# DummyLoad.net
KiCad netlist of a schematic drawn in EAGLE
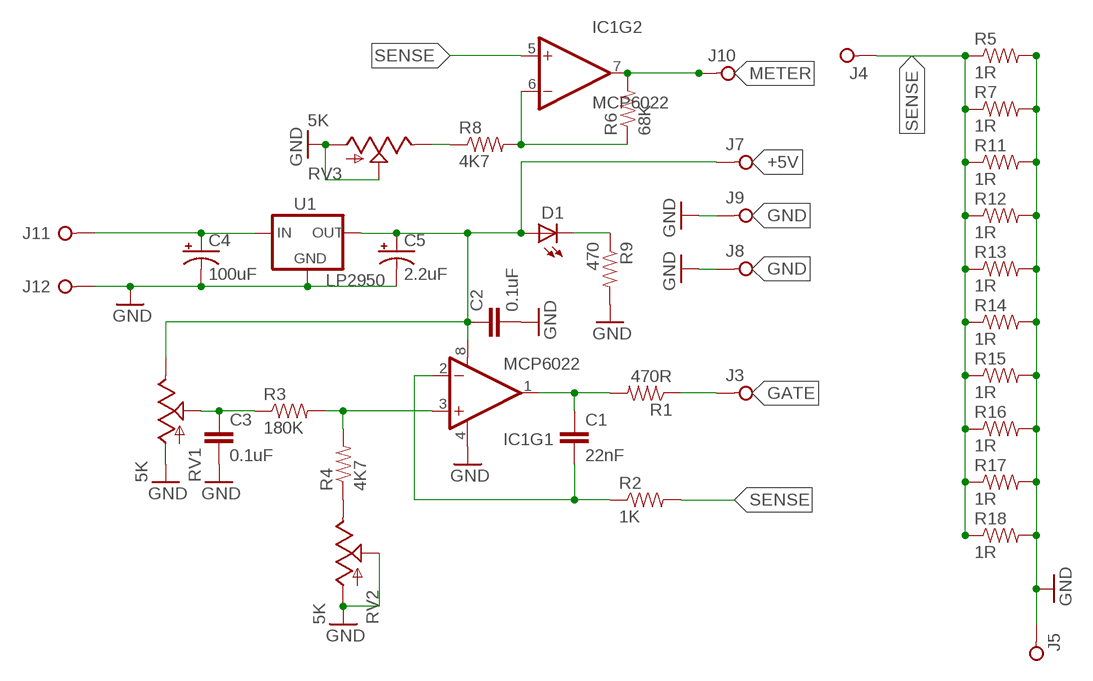
[diagram p0: schematic, sheet 1]

(export (version "E")
  (design (tool "Eeschema 10.0.6"))
  (components
    (comp (ref "C1")
      (value "22nF")
      (footprint "eagle-import:CAPACITOR-5MM")
      (libsource (lib "eagle-import") (part "CAPACITOR-5MM"))
    )
    (comp (ref "C2")
      (value "0.1uF")
      (footprint "eagle-import:CAPACITOR-5MM")
      (libsource (lib "eagle-import") (part "CAPACITOR-5MM"))
    )
    (comp (ref "C3")
      (value "0.1uF")
      (footprint "eagle-import:CAPACITOR-5MM")
      (libsource (lib "eagle-import") (part "CAPACITOR-5MM"))
    )
    (comp (ref "C4")
      (value "100uF")
      (footprint "eagle-import:CAP-POL-2.5-6")
      (libsource (lib "eagle-import") (part "CAP-POL-2.5-6"))
    )
    (comp (ref "C5")
      (value "2.2uF")
      (footprint "eagle-import:CAP-POL-2.5-5")
      (libsource (lib "eagle-import") (part "CAP-POL-2.5-5"))
    )
    (comp (ref "D1")
      (value "LED-5MM")
      (footprint "eagle-import:LED5MM")
      (libsource (lib "eagle-import") (part "LED-5MM"))
    )
    (comp (ref "IC1")
      (value "MCP6022")
      (footprint "eagle-import:DIP08")
      (libsource (lib "eagle-import") (part "MCP6022"))
    )
    (comp (ref "J1")
      (value "PINHD-1X2")
      (footprint "eagle-import:1X02")
      (libsource (lib "eagle-import") (part "PINHD-1X2"))
    )
    (comp (ref "J3")
      (value "PINHD-1X1")
      (footprint "eagle-import:1X01")
      (libsource (lib "eagle-import") (part "PINHD-1X1"))
    )
    (comp (ref "J4")
      (value "PINHD-1X1")
      (footprint "eagle-import:1X01")
      (libsource (lib "eagle-import") (part "PINHD-1X1"))
    )
    (comp (ref "J5")
      (value "PINHD-1X1")
      (footprint "eagle-import:1X01")
      (libsource (lib "eagle-import") (part "PINHD-1X1"))
    )
    (comp (ref "J7")
      (value "PINHD-1X1")
      (footprint "eagle-import:1X01")
      (libsource (lib "eagle-import") (part "PINHD-1X1"))
    )
    (comp (ref "J8")
      (value "PINHD-1X1")
      (footprint "eagle-import:1X01")
      (libsource (lib "eagle-import") (part "PINHD-1X1"))
    )
    (comp (ref "J9")
      (value "PINHD-1X1")
      (footprint "eagle-import:1X01")
      (libsource (lib "eagle-import") (part "PINHD-1X1"))
    )
    (comp (ref "J10")
      (value "PINHD-1X1")
      (footprint "eagle-import:1X01")
      (libsource (lib "eagle-import") (part "PINHD-1X1"))
    )
    (comp (ref "R1")
      (value "470R")
      (footprint "eagle-import:AXIAL-7.5MM")
      (libsource (lib "eagle-import") (part "RESISTOR-7.5MM"))
    )
    (comp (ref "R2")
      (value "1K")
      (footprint "eagle-import:AXIAL-7.5MM")
      (libsource (lib "eagle-import") (part "RESISTOR-7.5MM"))
    )
    (comp (ref "R3")
      (value "180K")
      (footprint "eagle-import:AXIAL-7.5MM")
      (libsource (lib "eagle-import") (part "RESISTOR-7.5MM"))
    )
    (comp (ref "R4")
      (value "4K7")
      (footprint "eagle-import:AXIAL-7.5MM")
      (libsource (lib "eagle-import") (part "RESISTOR-7.5MM"))
    )
    (comp (ref "R5")
      (value "1R")
      (footprint "eagle-import:AXIAL-7.5MM")
      (libsource (lib "eagle-import") (part "RESISTOR-7.5MM"))
    )
    (comp (ref "R6")
      (value "68K")
      (footprint "eagle-import:AXIAL-7.5MM")
      (libsource (lib "eagle-import") (part "RESISTOR-7.5MM"))
    )
    (comp (ref "R7")
      (value "1R")
      (footprint "eagle-import:AXIAL-7.5MM")
      (libsource (lib "eagle-import") (part "RESISTOR-7.5MM"))
    )
    (comp (ref "R8")
      (value "4K7")
      (footprint "eagle-import:AXIAL-7.5MM")
      (libsource (lib "eagle-import") (part "RESISTOR-7.5MM"))
    )
    (comp (ref "R9")
      (value "470")
      (footprint "eagle-import:AXIAL-7.5MM")
      (libsource (lib "eagle-import") (part "RESISTOR-7.5MM"))
    )
    (comp (ref "R11")
      (value "1R")
      (footprint "eagle-import:AXIAL-7.5MM")
      (libsource (lib "eagle-import") (part "RESISTOR-7.5MM"))
    )
    (comp (ref "R12")
      (value "1R")
      (footprint "eagle-import:AXIAL-7.5MM")
      (libsource (lib "eagle-import") (part "RESISTOR-7.5MM"))
    )
    (comp (ref "R13")
      (value "1R")
      (footprint "eagle-import:AXIAL-7.5MM")
      (libsource (lib "eagle-import") (part "RESISTOR-7.5MM"))
    )
    (comp (ref "R14")
      (value "1R")
      (footprint "eagle-import:AXIAL-7.5MM")
      (libsource (lib "eagle-import") (part "RESISTOR-7.5MM"))
    )
    (comp (ref "R15")
      (value "1R")
      (footprint "eagle-import:AXIAL-7.5MM")
      (libsource (lib "eagle-import") (part "RESISTOR-7.5MM"))
    )
    (comp (ref "R16")
      (value "1R")
      (footprint "eagle-import:AXIAL-7.5MM")
      (libsource (lib "eagle-import") (part "RESISTOR-7.5MM"))
    )
    (comp (ref "R17")
      (value "1R")
      (footprint "eagle-import:AXIAL-7.5MM")
      (libsource (lib "eagle-import") (part "RESISTOR-7.5MM"))
    )
    (comp (ref "R18")
      (value "1R")
      (footprint "eagle-import:AXIAL-7.5MM")
      (libsource (lib "eagle-import") (part "RESISTOR-7.5MM"))
    )
    (comp (ref "RV1")
      (value "5K")
      (footprint "eagle-import:1X03")
      (libsource (lib "eagle-import") (part "POT-OFFBRD"))
    )
    (comp (ref "RV2")
      (value "5K")
      (footprint "eagle-import:TRIM_POT")
      (libsource (lib "eagle-import") (part "POTTRIM"))
    )
    (comp (ref "RV3")
      (value "5K")
      (footprint "eagle-import:TRIM_POT")
      (libsource (lib "eagle-import") (part "POTTRIM"))
    )
    (comp (ref "U1")
      (value "LP2950")
      (footprint "eagle-import:TO92-INLINE")
      (libsource (lib "eagle-import") (part "LP2950"))
    )
  )
  (nets
    (net (code "1") (name "+5V") (class "Default")
      (node (ref "C2") (pin "1") (pinfunction "1_1") (pintype "passive"))
      (node (ref "C5") (pin "+") (pinfunction "+_+") (pintype "passive"))
      (node (ref "D1") (pin "A") (pinfunction "A_A") (pintype "passive"))
      (node (ref "IC1") (pin "8") (pinfunction "V+_8") (pintype "power_in"))
      (node (ref "J7") (pin "1") (pinfunction "KL_1") (pintype "passive"))
      (node (ref "RV1") (pin "3") (pinfunction "E_3") (pintype "passive"))
      (node (ref "U1") (pin "1") (pinfunction "OUT_1") (pintype "passive"))
    )
    (net (code "2") (name "GATE") (class "Default")
      (node (ref "J3") (pin "1") (pinfunction "KL_1") (pintype "passive"))
      (node (ref "R1") (pin "P$1") (pinfunction "1_P$1") (pintype "passive"))
    )
    (net (code "3") (name "GND") (class "Default")
      (node (ref "C2") (pin "2") (pinfunction "2_2") (pintype "passive"))
      (node (ref "C3") (pin "2") (pinfunction "2_2") (pintype "passive"))
      (node (ref "C4") (pin "-") (pinfunction "-_-") (pintype "passive"))
      (node (ref "C5") (pin "-") (pinfunction "-_-") (pintype "passive"))
      (node (ref "IC1") (pin "4") (pinfunction "V-_4") (pintype "power_in"))
      (node (ref "J1") (pin "2") (pinfunction "KL_2") (pintype "passive"))
      (node (ref "J5") (pin "1") (pinfunction "KL_1") (pintype "passive"))
      (node (ref "J8") (pin "1") (pinfunction "KL_1") (pintype "passive"))
      (node (ref "J9") (pin "1") (pinfunction "KL_1") (pintype "passive"))
      (node (ref "R11") (pin "P$2") (pinfunction "2_P$2") (pintype "passive"))
      (node (ref "R12") (pin "P$2") (pinfunction "2_P$2") (pintype "passive"))
      (node (ref "R13") (pin "P$2") (pinfunction "2_P$2") (pintype "passive"))
      (node (ref "R14") (pin "P$2") (pinfunction "2_P$2") (pintype "passive"))
      (node (ref "R15") (pin "P$2") (pinfunction "2_P$2") (pintype "passive"))
      (node (ref "R16") (pin "P$2") (pinfunction "2_P$2") (pintype "passive"))
      (node (ref "R17") (pin "P$2") (pinfunction "2_P$2") (pintype "passive"))
      (node (ref "R18") (pin "P$2") (pinfunction "2_P$2") (pintype "passive"))
      (node (ref "R5") (pin "P$2") (pinfunction "2_P$2") (pintype "passive"))
      (node (ref "R7") (pin "P$2") (pinfunction "2_P$2") (pintype "passive"))
      (node (ref "R9") (pin "P$2") (pinfunction "2_P$2") (pintype "passive"))
      (node (ref "RV1") (pin "1") (pinfunction "A_1") (pintype "passive"))
      (node (ref "RV2") (pin "1") (pinfunction "S_1") (pintype "passive"))
      (node (ref "RV2") (pin "3") (pinfunction "A_3") (pintype "passive"))
      (node (ref "RV3") (pin "1") (pinfunction "S_1") (pintype "passive"))
      (node (ref "RV3") (pin "3") (pinfunction "A_3") (pintype "passive"))
      (node (ref "U1") (pin "2") (pinfunction "GND_2") (pintype "input"))
    )
    (net (code "4") (name "METER") (class "Default")
      (node (ref "IC1") (pin "7") (pinfunction "OUT_7") (pintype "output"))
      (node (ref "J10") (pin "1") (pinfunction "KL_1") (pintype "passive"))
      (node (ref "R6") (pin "P$2") (pinfunction "2_P$2") (pintype "passive"))
    )
    (net (code "5") (name "Net-(D1-C)") (class "Default")
      (node (ref "D1") (pin "K") (pinfunction "C_K") (pintype "passive"))
      (node (ref "R9") (pin "P$1") (pinfunction "1_P$1") (pintype "passive"))
    )
    (net (code "6") (name "Net-(IC1A-+IN)") (class "Default")
      (node (ref "IC1") (pin "3") (pinfunction "+IN_3") (pintype "input"))
      (node (ref "R3") (pin "P$2") (pinfunction "2_P$2") (pintype "passive"))
      (node (ref "R4") (pin "P$2") (pinfunction "2_P$2") (pintype "passive"))
    )
    (net (code "7") (name "Net-(IC1A--IN)") (class "Default")
      (node (ref "C1") (pin "2") (pinfunction "2_2") (pintype "passive"))
      (node (ref "IC1") (pin "2") (pinfunction "-IN_2") (pintype "input"))
      (node (ref "R2") (pin "P$1") (pinfunction "1_P$1") (pintype "passive"))
    )
    (net (code "8") (name "Net-(IC1A-OUT)") (class "Default")
      (node (ref "C1") (pin "1") (pinfunction "1_1") (pintype "passive"))
      (node (ref "IC1") (pin "1") (pinfunction "OUT_1") (pintype "output"))
      (node (ref "R1") (pin "P$2") (pinfunction "2_P$2") (pintype "passive"))
    )
    (net (code "9") (name "Net-(IC1B--IN)") (class "Default")
      (node (ref "IC1") (pin "6") (pinfunction "-IN_6") (pintype "input"))
      (node (ref "R6") (pin "P$1") (pinfunction "1_P$1") (pintype "passive"))
      (node (ref "R8") (pin "P$2") (pinfunction "2_P$2") (pintype "passive"))
    )
    (net (code "10") (name "Net-(J1A-KL)") (class "Default")
      (node (ref "C4") (pin "+") (pinfunction "+_+") (pintype "passive"))
      (node (ref "J1") (pin "1") (pinfunction "KL_1") (pintype "passive"))
      (node (ref "U1") (pin "3") (pinfunction "IN_3") (pintype "input"))
    )
    (net (code "11") (name "Net-(R3-1)") (class "Default")
      (node (ref "C3") (pin "1") (pinfunction "1_1") (pintype "passive"))
      (node (ref "R3") (pin "P$1") (pinfunction "1_P$1") (pintype "passive"))
      (node (ref "RV1") (pin "2") (pinfunction "S_2") (pintype "passive"))
    )
    (net (code "12") (name "Net-(R4-1)") (class "Default")
      (node (ref "R4") (pin "P$1") (pinfunction "1_P$1") (pintype "passive"))
      (node (ref "RV2") (pin "2") (pinfunction "E_2") (pintype "passive"))
    )
    (net (code "13") (name "Net-(R8-1)") (class "Default")
      (node (ref "R8") (pin "P$1") (pinfunction "1_P$1") (pintype "passive"))
      (node (ref "RV3") (pin "2") (pinfunction "E_2") (pintype "passive"))
    )
    (net (code "14") (name "SENSE") (class "Default")
      (node (ref "IC1") (pin "5") (pinfunction "+IN_5") (pintype "input"))
      (node (ref "J4") (pin "1") (pinfunction "KL_1") (pintype "passive"))
      (node (ref "R11") (pin "P$1") (pinfunction "1_P$1") (pintype "passive"))
      (node (ref "R12") (pin "P$1") (pinfunction "1_P$1") (pintype "passive"))
      (node (ref "R13") (pin "P$1") (pinfunction "1_P$1") (pintype "passive"))
      (node (ref "R14") (pin "P$1") (pinfunction "1_P$1") (pintype "passive"))
      (node (ref "R15") (pin "P$1") (pinfunction "1_P$1") (pintype "passive"))
      (node (ref "R16") (pin "P$1") (pinfunction "1_P$1") (pintype "passive"))
      (node (ref "R17") (pin "P$1") (pinfunction "1_P$1") (pintype "passive"))
      (node (ref "R18") (pin "P$1") (pinfunction "1_P$1") (pintype "passive"))
      (node (ref "R2") (pin "P$2") (pinfunction "2_P$2") (pintype "passive"))
      (node (ref "R5") (pin "P$1") (pinfunction "1_P$1") (pintype "passive"))
      (node (ref "R7") (pin "P$1") (pinfunction "1_P$1") (pintype "passive"))
    )
  )
)
